# uSD.net
KiCad netlist of a schematic drawn in Altium Designer
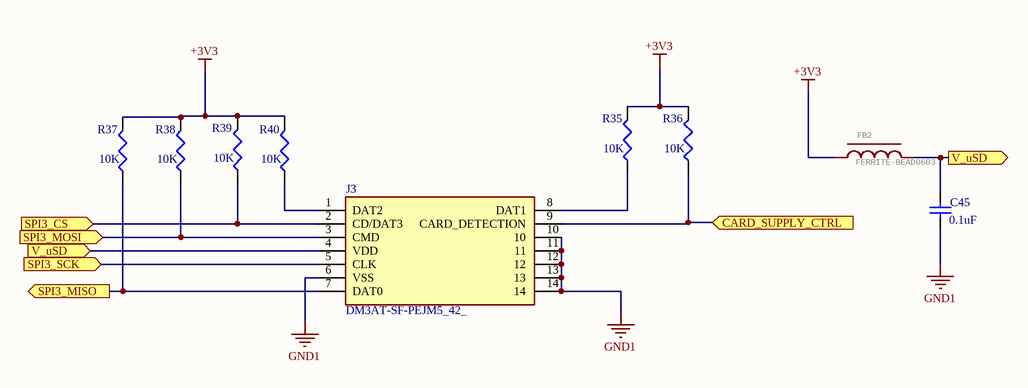
[diagram p0: uSD.SchDoc]

(export (version "E")
  (design (tool "Eeschema 10.0.6"))
  (components
    (comp (ref "C45")
      (value "0.1uF")
      (footprint "1608[0603]")
      (description "Capacitor (Semiconductor SIM Model)")
      (fields (field (name "Comment") "Cap Semi") (field (name "PUBLISHER") "Altium Limited"))
      (libsource (lib "Miscellaneous Devices") (part "Cap Semi"))
    )
    (comp (ref "FB2")
      (value "FERRITE-BEAD0603")
      (footprint "0603_INCH")
      (fields (field (name "LIBRARYNAME") "COMPAQ"))
      (libsource (lib "COMPAC (1)") (part "FERRITE-BEAD0603"))
    )
    (comp (ref "J3")
      (value "DM3AT-SF-PEJM5_42_")
      (footprint "SamacSys:DM3ATSFPEJM542")
      (description "Connector")
      (fields
        (field (name "MANUFACTURER_PART_NUMBER") "DM3AT-SF-PEJM5(42)")
        (field (name "MOUSER PART NUMBER") "798-DM3AT-SF-PEJM542")
      )
      (libsource (lib "SamacSys") (part "DM3AT-SF-PEJM5_42_"))
    )
    (comp (ref "R35")
      (value "10K")
      (footprint "J1-0603")
      (description "Resistor")
      (fields (field (name "Comment") "Res3") (field (name "PUBLISHER") "Altium Limited"))
      (libsource (lib "Miscellaneous Devices") (part "Res3"))
    )
    (comp (ref "R36")
      (value "10K")
      (footprint "J1-0603")
      (description "Resistor")
      (fields (field (name "Comment") "Res3") (field (name "PUBLISHER") "Altium Limited"))
      (libsource (lib "Miscellaneous Devices") (part "Res3"))
    )
    (comp (ref "R37")
      (value "10K")
      (footprint "J1-0603")
      (description "Resistor")
      (fields (field (name "Comment") "Res3") (field (name "PUBLISHER") "Altium Limited"))
      (libsource (lib "Miscellaneous Devices") (part "Res3"))
    )
    (comp (ref "R38")
      (value "10K")
      (footprint "J1-0603")
      (description "Resistor")
      (fields (field (name "Comment") "Res3") (field (name "PUBLISHER") "Altium Limited"))
      (libsource (lib "Miscellaneous Devices") (part "Res3"))
    )
    (comp (ref "R39")
      (value "10K")
      (footprint "J1-0603")
      (description "Resistor")
      (fields (field (name "Comment") "Res3") (field (name "PUBLISHER") "Altium Limited"))
      (libsource (lib "Miscellaneous Devices") (part "Res3"))
    )
    (comp (ref "R40")
      (value "10K")
      (footprint "J1-0603")
      (description "Resistor")
      (fields (field (name "Comment") "Res3") (field (name "PUBLISHER") "Altium Limited"))
      (libsource (lib "Miscellaneous Devices") (part "Res3"))
    )
  )
  (nets
    (net (code "1") (name "+3V3") (class "Default")
      (node (ref "FB2") (pin "1") (pinfunction "1_1") (pintype "passive"))
      (node (ref "R35") (pin "2") (pinfunction "2_2") (pintype "passive"))
      (node (ref "R36") (pin "2") (pinfunction "2_2") (pintype "passive"))
      (node (ref "R37") (pin "2") (pinfunction "2_2") (pintype "passive"))
      (node (ref "R38") (pin "2") (pinfunction "2_2") (pintype "passive"))
      (node (ref "R39") (pin "2") (pinfunction "2_2") (pintype "passive"))
      (node (ref "R40") (pin "2") (pinfunction "2_2") (pintype "passive"))
    )
    (net (code "2") (name "/CARD_SUPPLY_CTRL") (class "Default")
      (node (ref "J3") (pin "9") (pinfunction "CARD_DETECTION_9") (pintype "passive"))
      (node (ref "R36") (pin "1") (pinfunction "1_1") (pintype "passive"))
    )
    (net (code "3") (name "/SPI3_CS") (class "Default")
      (node (ref "J3") (pin "2") (pinfunction "CD/DAT3_2") (pintype "passive"))
      (node (ref "R39") (pin "1") (pinfunction "1_1") (pintype "passive"))
    )
    (net (code "4") (name "/SPI3_MISO") (class "Default")
      (node (ref "J3") (pin "7") (pinfunction "DAT0_7") (pintype "passive"))
      (node (ref "R37") (pin "1") (pinfunction "1_1") (pintype "passive"))
    )
    (net (code "5") (name "/SPI3_MOSI") (class "Default")
      (node (ref "J3") (pin "3") (pinfunction "CMD_3") (pintype "passive"))
      (node (ref "R38") (pin "1") (pinfunction "1_1") (pintype "passive"))
    )
    (net (code "6") (name "/SPI3_SCK") (class "Default")
      (node (ref "J3") (pin "5") (pinfunction "CLK_5") (pintype "passive"))
    )
    (net (code "7") (name "/V_uSD") (class "Default")
      (node (ref "C45") (pin "2") (pinfunction "2_2") (pintype "passive"))
      (node (ref "FB2") (pin "2") (pinfunction "2_2") (pintype "passive"))
      (node (ref "J3") (pin "4") (pinfunction "VDD_4") (pintype "passive"))
    )
    (net (code "8") (name "GND1") (class "Default")
      (node (ref "C45") (pin "1") (pinfunction "1_1") (pintype "passive"))
      (node (ref "J3") (pin "10") (pinfunction "10_10") (pintype "passive"))
      (node (ref "J3") (pin "11") (pinfunction "11_11") (pintype "passive"))
      (node (ref "J3") (pin "12") (pinfunction "12_12") (pintype "passive"))
      (node (ref "J3") (pin "13") (pinfunction "13_13") (pintype "passive"))
      (node (ref "J3") (pin "14") (pinfunction "14_14") (pintype "passive"))
      (node (ref "J3") (pin "6") (pinfunction "VSS_6") (pintype "passive"))
    )
    (net (code "9") (name "Net-(J3-DAT1)") (class "Default")
      (node (ref "J3") (pin "8") (pinfunction "DAT1_8") (pintype "passive"))
      (node (ref "R35") (pin "1") (pinfunction "1_1") (pintype "passive"))
    )
    (net (code "10") (name "Net-(J3-DAT2)") (class "Default")
      (node (ref "J3") (pin "1") (pinfunction "DAT2_1") (pintype "passive"))
      (node (ref "R40") (pin "1") (pinfunction "1_1") (pintype "passive"))
    )
  )
)
